# GraduatedDesign_03.net
KiCad netlist of a schematic drawn in Altium Designer
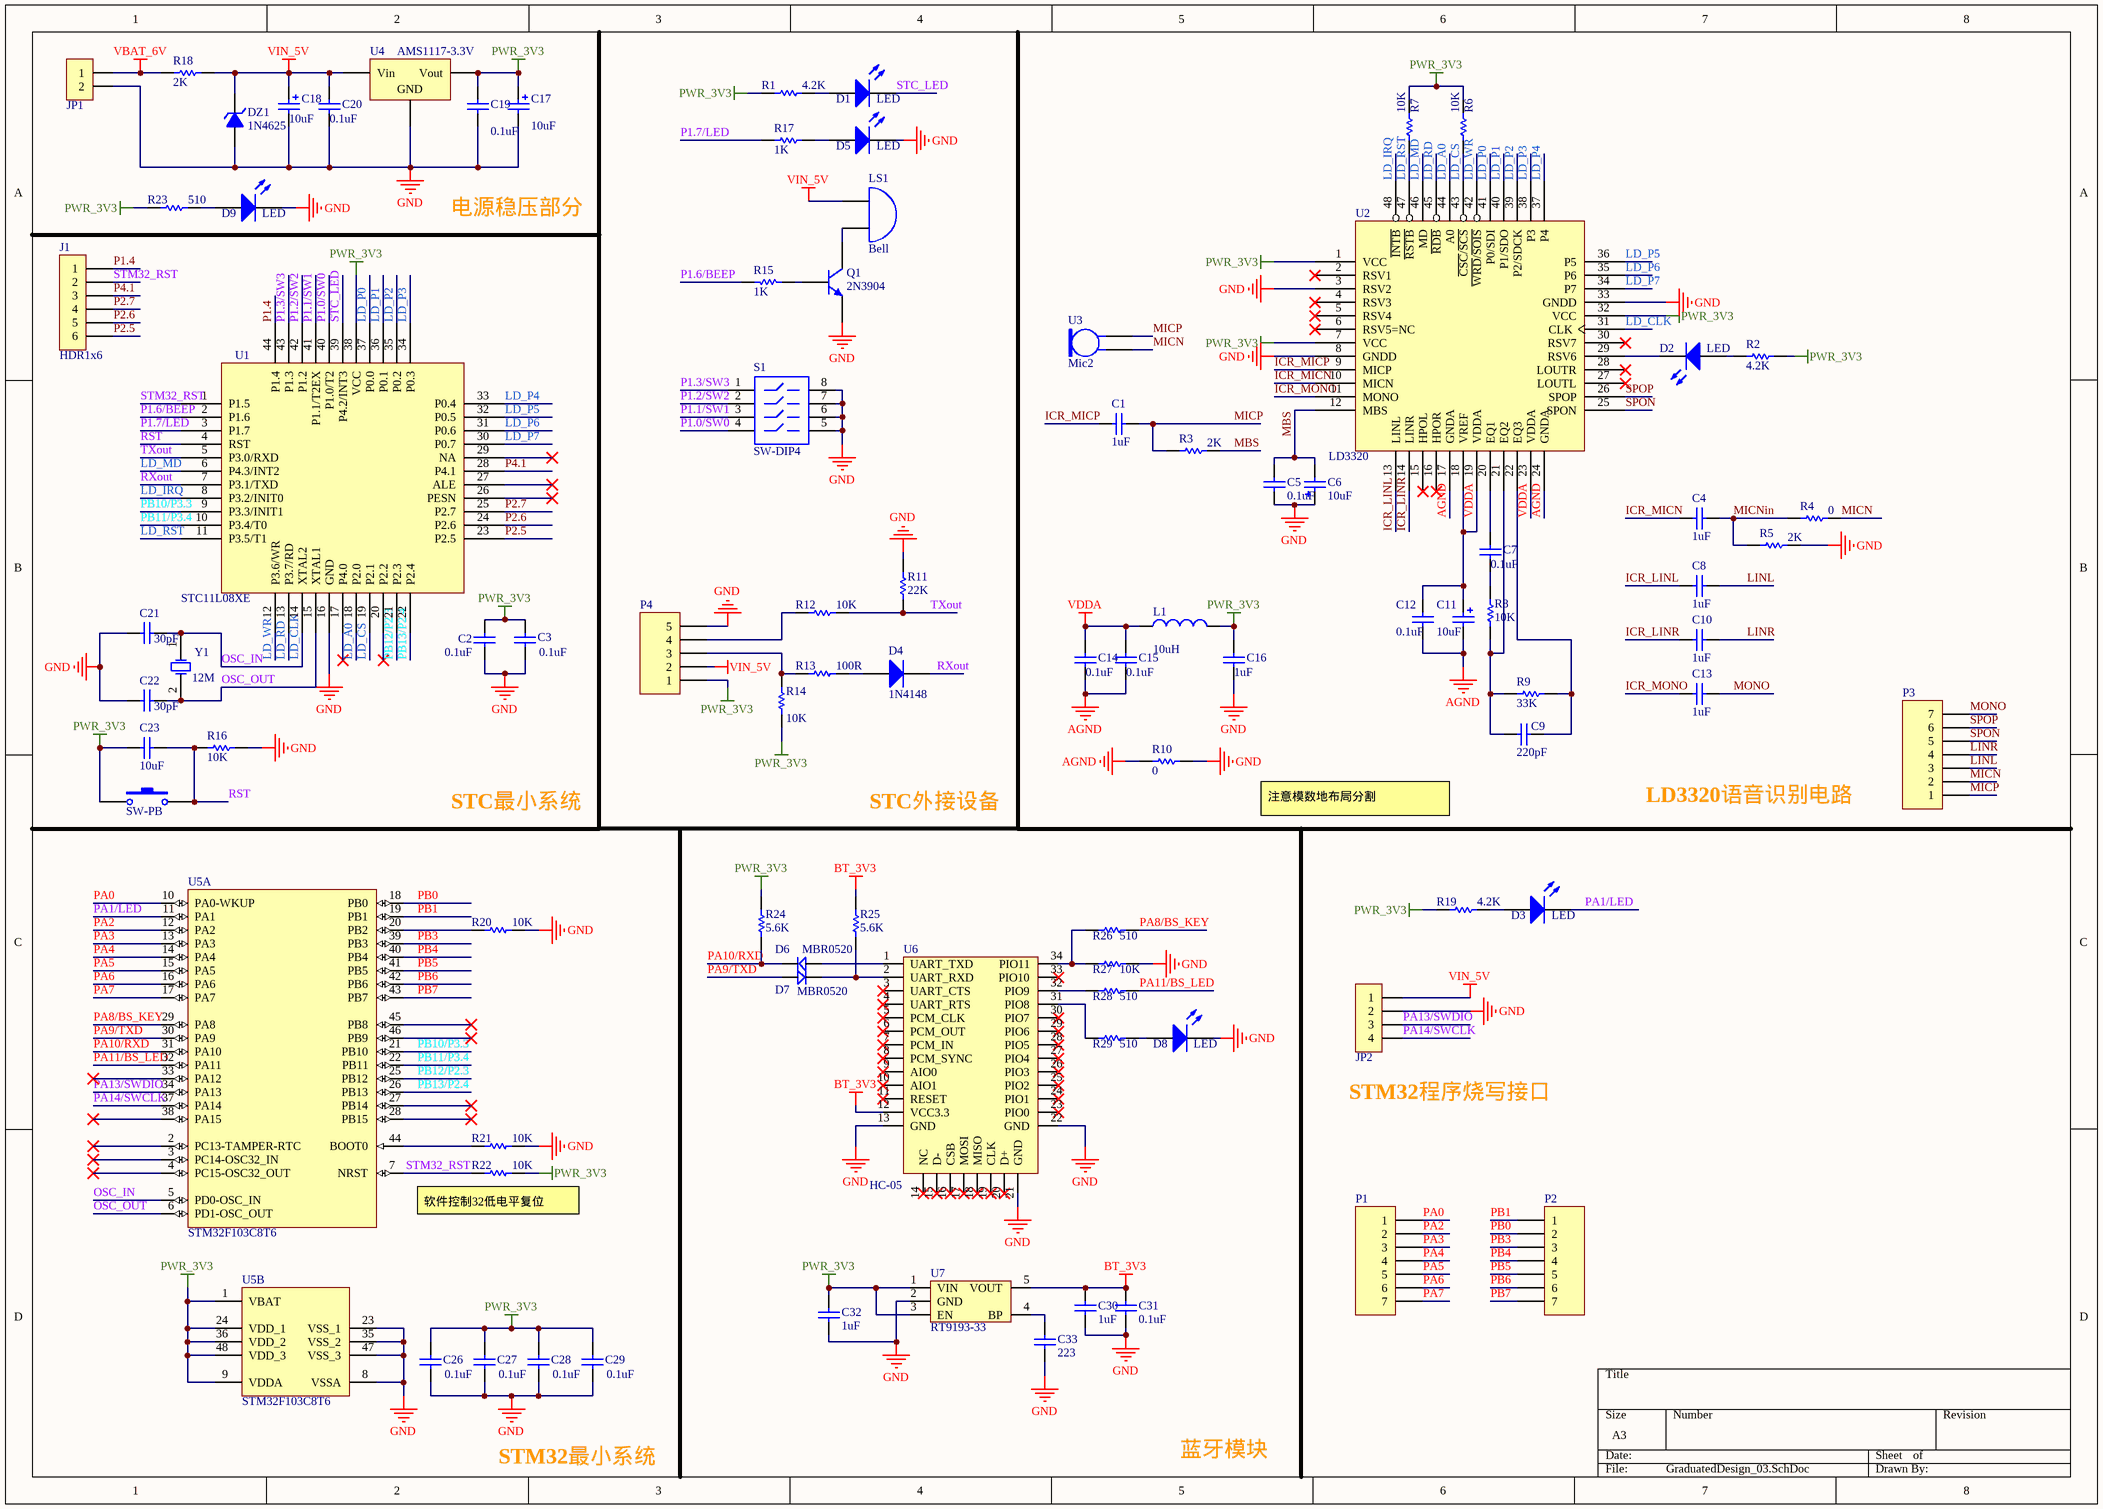
[diagram p0: GraduatedDesign_03.SchDoc]

(export (version "E")
  (design (tool "Eeschema 10.0.6"))
  (components
    (comp (ref "C1")
      (value "1uF")
      (footprint "C0603")
      (description "Capacitor")
      (fields (field (name "Comment") "Cap"))
      (libsource (lib "Miscellaneous Devices") (part "Cap"))
    )
    (comp (ref "C2")
      (value "0.1uF")
      (footprint "C0603")
      (description "Capacitor")
      (fields (field (name "Comment") "Cap"))
      (libsource (lib "Miscellaneous Devices") (part "Cap"))
    )
    (comp (ref "C3")
      (value "0.1uF")
      (footprint "C0603")
      (description "Capacitor")
      (fields (field (name "Comment") "Cap"))
      (libsource (lib "Miscellaneous Devices") (part "Cap"))
    )
    (comp (ref "C4")
      (value "1uF")
      (footprint "C0603")
      (description "Capacitor")
      (fields (field (name "Comment") "Cap"))
      (libsource (lib "Miscellaneous Devices") (part "Cap"))
    )
    (comp (ref "C5")
      (value "0.1uF")
      (footprint "C0603")
      (description "Capacitor")
      (fields (field (name "Comment") "Cap"))
      (libsource (lib "Miscellaneous Devices") (part "Cap"))
    )
    (comp (ref "C6")
      (value "10uF")
      (footprint "C3216")
      (description "Polarized Capacitor (Axial)")
      (fields (field (name "Comment") "Cap Pol2"))
      (libsource (lib "Miscellaneous Devices") (part "Cap Pol2"))
    )
    (comp (ref "C7")
      (value "0.1uF")
      (footprint "C0603")
      (description "Capacitor")
      (fields (field (name "Comment") "Cap"))
      (libsource (lib "Miscellaneous Devices") (part "Cap"))
    )
    (comp (ref "C8")
      (value "1uF")
      (footprint "C0603")
      (description "Capacitor")
      (fields (field (name "Comment") "Cap"))
      (libsource (lib "Miscellaneous Devices") (part "Cap"))
    )
    (comp (ref "C9")
      (value "220pF")
      (footprint "C0603")
      (description "Capacitor")
      (fields (field (name "Comment") "Cap"))
      (libsource (lib "Miscellaneous Devices") (part "Cap"))
    )
    (comp (ref "C10")
      (value "1uF")
      (footprint "C0603")
      (description "Capacitor")
      (fields (field (name "Comment") "Cap"))
      (libsource (lib "Miscellaneous Devices") (part "Cap"))
    )
    (comp (ref "C11")
      (value "10uF")
      (footprint "C3216")
      (description "Polarized Capacitor (Axial)")
      (fields (field (name "Comment") "Cap Pol2"))
      (libsource (lib "Miscellaneous Devices") (part "Cap Pol2"))
    )
    (comp (ref "C12")
      (value "0.1uF")
      (footprint "C0603")
      (description "Capacitor")
      (fields (field (name "Comment") "Cap"))
      (libsource (lib "Miscellaneous Devices") (part "Cap"))
    )
    (comp (ref "C13")
      (value "1uF")
      (footprint "C0603")
      (description "Capacitor")
      (fields (field (name "Comment") "Cap"))
      (libsource (lib "Miscellaneous Devices") (part "Cap"))
    )
    (comp (ref "C14")
      (value "0.1uF")
      (footprint "C0603")
      (description "Capacitor")
      (fields (field (name "Comment") "Cap"))
      (libsource (lib "Miscellaneous Devices") (part "Cap"))
    )
    (comp (ref "C15")
      (value "0.1uF")
      (footprint "C0603")
      (description "Capacitor")
      (fields (field (name "Comment") "Cap"))
      (libsource (lib "Miscellaneous Devices") (part "Cap"))
    )
    (comp (ref "C16")
      (value "1uF")
      (footprint "C0603")
      (description "Capacitor")
      (fields (field (name "Comment") "Cap"))
      (libsource (lib "Miscellaneous Devices") (part "Cap"))
    )
    (comp (ref "C17")
      (value "10uF")
      (footprint "C3216")
      (description "Polarized Capacitor (Axial)")
      (fields (field (name "Comment") "Cap Pol2"))
      (libsource (lib "Miscellaneous Devices") (part "Cap Pol2"))
    )
    (comp (ref "C18")
      (value "10uF")
      (footprint "C3216")
      (description "Polarized Capacitor (Axial)")
      (fields (field (name "Comment") "Cap Pol2"))
      (libsource (lib "Miscellaneous Devices") (part "Cap Pol2"))
    )
    (comp (ref "C19")
      (value "0.1uF")
      (footprint "C0603")
      (description "Capacitor")
      (fields (field (name "Comment") "Cap"))
      (libsource (lib "Miscellaneous Devices") (part "Cap"))
    )
    (comp (ref "C20")
      (value "0.1uF")
      (footprint "C0603")
      (description "Capacitor")
      (fields (field (name "Comment") "Cap"))
      (libsource (lib "Miscellaneous Devices") (part "Cap"))
    )
    (comp (ref "C21")
      (value "30pF")
      (footprint "C0603")
      (description "Capacitor")
      (fields (field (name "Comment") "Cap"))
      (libsource (lib "Miscellaneous Devices") (part "Cap"))
    )
    (comp (ref "C22")
      (value "30pF")
      (footprint "C0603")
      (description "Capacitor")
      (fields (field (name "Comment") "Cap"))
      (libsource (lib "Miscellaneous Devices") (part "Cap"))
    )
    (comp (ref "C23")
      (value "10uF")
      (footprint "C0603")
      (description "Capacitor")
      (fields (field (name "Comment") "Cap"))
      (libsource (lib "Miscellaneous Devices") (part "Cap"))
    )
    (comp (ref "C26")
      (value "0.1uF")
      (footprint "C0603")
      (description "Capacitor")
      (fields (field (name "Comment") "Cap"))
      (libsource (lib "Miscellaneous Devices") (part "Cap"))
    )
    (comp (ref "C27")
      (value "0.1uF")
      (footprint "C0603")
      (description "Capacitor")
      (fields (field (name "Comment") "Cap"))
      (libsource (lib "Miscellaneous Devices") (part "Cap"))
    )
    (comp (ref "C28")
      (value "0.1uF")
      (footprint "C0603")
      (description "Capacitor")
      (fields (field (name "Comment") "Cap"))
      (libsource (lib "Miscellaneous Devices") (part "Cap"))
    )
    (comp (ref "C29")
      (value "0.1uF")
      (footprint "C0603")
      (description "Capacitor")
      (fields (field (name "Comment") "Cap"))
      (libsource (lib "Miscellaneous Devices") (part "Cap"))
    )
    (comp (ref "C30")
      (value "1uF")
      (footprint "C0603")
      (description "Capacitor")
      (fields (field (name "Comment") "Cap"))
      (libsource (lib "Miscellaneous Devices") (part "Cap"))
    )
    (comp (ref "C31")
      (value "0.1uF")
      (footprint "C0603")
      (description "Capacitor")
      (fields (field (name "Comment") "Cap"))
      (libsource (lib "Miscellaneous Devices") (part "Cap"))
    )
    (comp (ref "C32")
      (value "1uF")
      (footprint "C0603")
      (description "Capacitor")
      (fields (field (name "Comment") "Cap"))
      (libsource (lib "Miscellaneous Devices") (part "Cap"))
    )
    (comp (ref "C33")
      (value "223")
      (footprint "C0603")
      (description "Capacitor")
      (fields (field (name "Comment") "Cap"))
      (libsource (lib "Miscellaneous Devices") (part "Cap"))
    )
    (comp (ref "D1")
      (value "LED")
      (footprint "0603LED_GREEN")
      (description "Typical INFRARED GaAs LED")
      (libsource (lib "Miscellaneous Devices") (part "LED0"))
    )
    (comp (ref "D2")
      (value "LED")
      (footprint "0603LED_RED")
      (description "Typical INFRARED GaAs LED")
      (libsource (lib "Miscellaneous Devices") (part "LED0"))
    )
    (comp (ref "D3")
      (value "LED")
      (footprint "0603LED_GREEN")
      (description "Typical INFRARED GaAs LED")
      (libsource (lib "Miscellaneous Devices") (part "LED0"))
    )
    (comp (ref "D4")
      (value "1N4148")
      (footprint "D1206")
      (description "High Conductance Fast Diode")
      (libsource (lib "Miscellaneous Devices") (part "Diode 1N4148"))
    )
    (comp (ref "D5")
      (value "LED")
      (footprint "0603LED_GREEN")
      (description "Typical INFRARED GaAs LED")
      (libsource (lib "Miscellaneous Devices") (part "LED0"))
    )
    (comp (ref "D6")
      (value "MBR0520")
      (footprint "SOD-123")
      (description "1N4148")
      (libsource (lib "ATK-HC05-V1.3") (part "D"))
    )
    (comp (ref "D7")
      (value "MBR0520")
      (footprint "SOD-123")
      (description "1N4148")
      (libsource (lib "ATK-HC05-V1.3") (part "D"))
    )
    (comp (ref "D8")
      (value "LED")
      (footprint "0603LED_GREEN")
      (description "Typical INFRARED GaAs LED")
      (libsource (lib "Miscellaneous Devices") (part "LED0"))
    )
    (comp (ref "D9")
      (value "LED")
      (footprint "0603LED_GREEN")
      (description "Typical INFRARED GaAs LED")
      (libsource (lib "Miscellaneous Devices") (part "LED0"))
    )
    (comp (ref "DZ1")
      (value "1N4625")
      (footprint "SOD-323")
      (description "5.1V/0.5W稳压管")
      (libsource (lib "二极管-整流桥") (part "1N4625"))
    )
    (comp (ref "J1")
      (value "HDR1x6")
      (footprint "HDR1X6")
      (description "Connector")
      (libsource (lib "General") (part "HDR1x6"))
    )
    (comp (ref "JP1")
      (value "HDR-1X2")
      (footprint "HDR1X2")
      (description "2P接插件")
      (libsource (lib "接插件") (part "Header 2"))
    )
    (comp (ref "JP2")
      (value "HDR-1X4")
      (footprint "HDR1X4")
      (description "4P接插件")
      (libsource (lib "接插件") (part "Header 4"))
    )
    (comp (ref "L1")
      (value "10uH")
      (footprint "L0805")
      (description "Inductor")
      (libsource (lib "Miscellaneous Devices") (part "Inductor"))
    )
    (comp (ref "LS1")
      (value "Bell")
      (footprint "BELL")
      (description "Electrical Bell")
      (libsource (lib "Miscellaneous Devices") (part "Bell"))
    )
    (comp (ref "P1")
      (value "Header 7H")
      (footprint "Miscellaneous Connectors:HDR1X7")
      (description "Header, 7-Pin, Right Angle")
      (libsource (lib "") (part "Header 7H_1"))
    )
    (comp (ref "P2")
      (value "Header 7H")
      (footprint "Miscellaneous Connectors:HDR1X7")
      (description "Header, 7-Pin, Right Angle")
      (libsource (lib "") (part "Header 7H_2"))
    )
    (comp (ref "P3")
      (value "Header 7H")
      (footprint "Miscellaneous Connectors:HDR1X7")
      (description "Header, 7-Pin, Right Angle")
      (libsource (lib "Miscellaneous Connectors") (part "Header 7H"))
    )
    (comp (ref "P4")
      (value "Header 5H")
      (footprint "Miscellaneous Connectors:HDR1X5")
      (description "Header, 5-Pin, Right Angle")
      (libsource (lib "Miscellaneous Connectors") (part "Header 5H"))
    )
    (comp (ref "Q1")
      (value "2N3904")
      (footprint "SOT-23")
      (description "NPN General Purpose Amplifier")
      (libsource (lib "Miscellaneous Devices") (part "2N3904"))
    )
    (comp (ref "R1")
      (value "4.2K")
      (footprint "R0603")
      (description "Resistor")
      (fields (field (name "Comment") "Res1"))
      (libsource (lib "Miscellaneous Devices") (part "Res1"))
    )
    (comp (ref "R2")
      (value "4.2K")
      (footprint "R0603")
      (description "Resistor")
      (fields (field (name "Comment") "Res1"))
      (libsource (lib "Miscellaneous Devices") (part "Res1"))
    )
    (comp (ref "R3")
      (value "2K")
      (footprint "R0603")
      (description "Resistor")
      (fields (field (name "Comment") "Res1"))
      (libsource (lib "Miscellaneous Devices") (part "Res1"))
    )
    (comp (ref "R4")
      (value "0")
      (footprint "R0603")
      (description "Resistor")
      (fields (field (name "Comment") "Res1"))
      (libsource (lib "Miscellaneous Devices") (part "Res1"))
    )
    (comp (ref "R5")
      (value "2K")
      (footprint "R0603")
      (description "Resistor")
      (fields (field (name "Comment") "Res1"))
      (libsource (lib "Miscellaneous Devices") (part "Res1"))
    )
    (comp (ref "R6")
      (value "10K")
      (footprint "R0603")
      (description "Resistor")
      (fields (field (name "Comment") "Res1"))
      (libsource (lib "Miscellaneous Devices") (part "Res1"))
    )
    (comp (ref "R7")
      (value "10K")
      (footprint "R0603")
      (description "Resistor")
      (fields (field (name "Comment") "Res1"))
      (libsource (lib "Miscellaneous Devices") (part "Res1"))
    )
    (comp (ref "R8")
      (value "10K")
      (footprint "R0603")
      (description "Resistor")
      (fields (field (name "Comment") "Res1"))
      (libsource (lib "Miscellaneous Devices") (part "Res1"))
    )
    (comp (ref "R9")
      (value "33K")
      (footprint "R0603")
      (description "Resistor")
      (fields (field (name "Comment") "Res1"))
      (libsource (lib "Miscellaneous Devices") (part "Res1"))
    )
    (comp (ref "R10")
      (value "0")
      (footprint "R0603")
      (description "Resistor")
      (fields (field (name "Comment") "Res1"))
      (libsource (lib "Miscellaneous Devices") (part "Res1"))
    )
    (comp (ref "R11")
      (value "22K")
      (footprint "R0603")
      (description "Semiconductor Resistor")
      (fields (field (name "Comment") "Res Semi"))
      (libsource (lib "Miscellaneous Devices") (part "Res Semi"))
    )
    (comp (ref "R12")
      (value "10K")
      (footprint "R0603")
      (description "Semiconductor Resistor")
      (fields (field (name "Comment") "Res Semi"))
      (libsource (lib "Miscellaneous Devices") (part "Res Semi"))
    )
    (comp (ref "R13")
      (value "100R")
      (footprint "R0603")
      (description "Semiconductor Resistor")
      (fields (field (name "Comment") "Res Semi"))
      (libsource (lib "Miscellaneous Devices") (part "Res Semi"))
    )
    (comp (ref "R14")
      (value "10K")
      (footprint "R0603")
      (description "Semiconductor Resistor")
      (fields (field (name "Comment") "Res Semi"))
      (libsource (lib "Miscellaneous Devices") (part "Res Semi"))
    )
    (comp (ref "R15")
      (value "1K")
      (footprint "R0603")
      (description "Resistor")
      (fields (field (name "Comment") "Res1"))
      (libsource (lib "Miscellaneous Devices") (part "Res1"))
    )
    (comp (ref "R16")
      (value "10K")
      (footprint "R0603")
      (description "Resistor")
      (fields (field (name "Comment") "Res1"))
      (libsource (lib "Miscellaneous Devices") (part "Res1"))
    )
    (comp (ref "R17")
      (value "1K")
      (footprint "R0603")
      (description "Resistor")
      (fields (field (name "Comment") "Res1"))
      (libsource (lib "Miscellaneous Devices") (part "Res1"))
    )
    (comp (ref "R18")
      (value "2K")
      (footprint "R0603")
      (description "Resistor")
      (fields (field (name "Comment") "Res1"))
      (libsource (lib "Miscellaneous Devices") (part "Res1"))
    )
    (comp (ref "R19")
      (value "4.2K")
      (footprint "R0603")
      (description "Resistor")
      (fields (field (name "Comment") "Res1"))
      (libsource (lib "Miscellaneous Devices") (part "Res1"))
    )
    (comp (ref "R20")
      (value "10K")
      (footprint "R0603")
      (description "Resistor")
      (fields (field (name "Comment") "Res1"))
      (libsource (lib "Miscellaneous Devices") (part "Res1"))
    )
    (comp (ref "R21")
      (value "10K")
      (footprint "R0603")
      (description "Resistor")
      (fields (field (name "Comment") "Res1"))
      (libsource (lib "Miscellaneous Devices") (part "Res1"))
    )
    (comp (ref "R22")
      (value "10K")
      (footprint "R0603")
      (description "Resistor")
      (fields (field (name "Comment") "Res1"))
      (libsource (lib "Miscellaneous Devices") (part "Res1"))
    )
    (comp (ref "R23")
      (value "510")
      (footprint "R0603")
      (description "Resistor")
      (fields (field (name "Comment") "Res1"))
      (libsource (lib "Miscellaneous Devices") (part "Res1"))
    )
    (comp (ref "R24")
      (value "5.6K")
      (footprint "R0603")
      (description "Resistor")
      (fields (field (name "Comment") "Res1"))
      (libsource (lib "Miscellaneous Devices") (part "Res1"))
    )
    (comp (ref "R25")
      (value "5.6K")
      (footprint "R0603")
      (description "Resistor")
      (fields (field (name "Comment") "Res1"))
      (libsource (lib "Miscellaneous Devices") (part "Res1"))
    )
    (comp (ref "R26")
      (value "510")
      (footprint "R0603")
      (description "Resistor")
      (fields (field (name "Comment") "Res1"))
      (libsource (lib "Miscellaneous Devices") (part "Res1"))
    )
    (comp (ref "R27")
      (value "10K")
      (footprint "R0603")
      (description "Resistor")
      (fields (field (name "Comment") "Res1"))
      (libsource (lib "Miscellaneous Devices") (part "Res1"))
    )
    (comp (ref "R28")
      (value "510")
      (footprint "R0603")
      (description "Resistor")
      (fields (field (name "Comment") "Res1"))
      (libsource (lib "Miscellaneous Devices") (part "Res1"))
    )
    (comp (ref "R29")
      (value "510")
      (footprint "R0603")
      (description "Resistor")
      (fields (field (name "Comment") "Res1"))
      (libsource (lib "Miscellaneous Devices") (part "Res1"))
    )
    (comp (ref "S1")
      (value "SW-DIP4")
      (footprint "DIP-8")
      (description "DIP Switch")
      (libsource (lib "Miscellaneous Devices") (part "SW-DIP4"))
    )
    (comp (ref "S2")
      (value "SW-PB")
      (footprint "SPST-2")
      (description "Switch")
      (libsource (lib "Miscellaneous Devices") (part "SW-PB"))
    )
    (comp (ref "U1")
      (value "STC11L08XE")
      (footprint "QFP-44")
      (libsource (lib "STC11L08XE") (part "STC11L08XE"))
    )
    (comp (ref "U2") (value "LD3320") (footprint "LD3320A") (libsource (lib "STC11L08XE") (part "LD3320A")))
    (comp (ref "U3")
      (value "Mic2")
      (footprint "PIN2")
      (description "Microphone")
      (libsource (lib "Miscellaneous Devices") (part "Mic2"))
    )
    (comp (ref "U4")
      (value "AMS1117-3.3V")
      (footprint "SOT223")
      (description "Voltage Regulator")
      (libsource (lib "Miscellaneous Devices") (part "Volt Reg"))
    )
    (comp (ref "U5")
      (value "STM32F103C8T6")
      (footprint "LQFP48_M")
      (libsource (lib "STMicroelectronics STM32 F1") (part "STM32F103C8T6"))
    )
    (comp (ref "U6")
      (value "HC-05")
      (footprint "HC-0x")
      (description "蓝牙串口模块")
      (libsource (lib "ATK-HC05-V1.3") (part "HC-05"))
    )
    (comp (ref "U7")
      (value "RT9193-33")
      (footprint "SOT-23-5")
      (description "3.3V超低压差LDO")
      (libsource (lib "ATK-HC05-V1.3") (part "RT9193-33"))
    )
    (comp (ref "Y1")
      (value "12M")
      (footprint "49/S_N")
      (description "Crystal Oscillator")
      (libsource (lib "Miscellaneous Devices") (part "XTAL"))
    )
  )
  (nets
    (net (code "1") (name "/ICR_LINL") (class "Default")
      (node (ref "C8") (pin "1") (pinfunction "1_1") (pintype "passive"))
      (node (ref "U2") (pin "13") (pinfunction "LINL_13") (pintype "passive"))
    )
    (net (code "2") (name "/ICR_LINR") (class "Default")
      (node (ref "C10") (pin "1") (pinfunction "1_1") (pintype "passive"))
      (node (ref "U2") (pin "14") (pinfunction "LINR_14") (pintype "passive"))
    )
    (net (code "3") (name "/ICR_MICN") (class "Default")
      (node (ref "C4") (pin "1") (pinfunction "1_1") (pintype "passive"))
      (node (ref "U2") (pin "10") (pinfunction "MICN_10") (pintype "passive"))
    )
    (net (code "4") (name "/ICR_MICP") (class "Default")
      (node (ref "C1") (pin "1") (pinfunction "1_1") (pintype "passive"))
      (node (ref "U2") (pin "9") (pinfunction "MICP_9") (pintype "passive"))
    )
    (net (code "5") (name "/ICR_MONO") (class "Default")
      (node (ref "C13") (pin "1") (pinfunction "1_1") (pintype "passive"))
      (node (ref "U2") (pin "11") (pinfunction "MONO_11") (pintype "passive"))
    )
    (net (code "6") (name "/LD_A0") (class "Default")
      (node (ref "U1") (pin "18") (pinfunction "P2.0_18") (pintype "passive"))
      (node (ref "U2") (pin "44") (pinfunction "A0_44") (pintype "passive"))
    )
    (net (code "7") (name "/LD_CLK") (class "Default")
      (node (ref "C21") (pin "2") (pinfunction "2_2") (pintype "passive"))
      (node (ref "U1") (pin "14") (pinfunction "XTAL2_14") (pintype "passive"))
      (node (ref "U2") (pin "31") (pinfunction "CLK_31") (pintype "passive"))
      (node (ref "U5") (pin "5") (pinfunction "PD0-OSC_IN_5") (pintype "bidirectional"))
      (node (ref "Y1") (pin "1") (pinfunction "OSC1_1") (pintype "passive"))
    )
    (net (code "8") (name "/LD_CS") (class "Default")
      (node (ref "R6") (pin "2") (pinfunction "2_2") (pintype "passive"))
      (node (ref "U1") (pin "19") (pinfunction "P2.1_19") (pintype "passive"))
      (node (ref "U2") (pin "43") (pinfunction "~{CSC}/~{SCS}_43") (pintype "passive"))
    )
    (net (code "9") (name "/LD_IRQ") (class "Default")
      (node (ref "U1") (pin "8") (pinfunction "P3.2/INIT0_8") (pintype "passive"))
      (node (ref "U2") (pin "48") (pinfunction "~{INTB}_48") (pintype "passive"))
    )
    (net (code "10") (name "/LD_MD") (class "Default")
      (node (ref "U1") (pin "6") (pinfunction "P4.3/INT2_6") (pintype "passive"))
      (node (ref "U2") (pin "46") (pinfunction "MD_46") (pintype "passive"))
    )
    (net (code "11") (name "/LD_P0") (class "Default")
      (node (ref "U1") (pin "37") (pinfunction "P0.0_37") (pintype "passive"))
      (node (ref "U2") (pin "41") (pinfunction "P0/SDI_41") (pintype "passive"))
    )
    (net (code "12") (name "/LD_P1") (class "Default")
      (node (ref "U1") (pin "36") (pinfunction "P0.1_36") (pintype "passive"))
      (node (ref "U2") (pin "40") (pinfunction "P1/SDO_40") (pintype "passive"))
    )
    (net (code "13") (name "/LD_P2") (class "Default")
      (node (ref "U1") (pin "35") (pinfunction "P0.2_35") (pintype "passive"))
      (node (ref "U2") (pin "39") (pinfunction "P2/SDCK_39") (pintype "passive"))
    )
    (net (code "14") (name "/LD_P3") (class "Default")
      (node (ref "U1") (pin "34") (pinfunction "P0.3_34") (pintype "passive"))
      (node (ref "U2") (pin "38") (pinfunction "P3_38") (pintype "passive"))
    )
    (net (code "15") (name "/LD_P4") (class "Default")
      (node (ref "U1") (pin "33") (pinfunction "P0.4_33") (pintype "passive"))
      (node (ref "U2") (pin "37") (pinfunction "P4_37") (pintype "passive"))
    )
    (net (code "16") (name "/LD_P5") (class "Default")
      (node (ref "U1") (pin "32") (pinfunction "P0.5_32") (pintype "passive"))
      (node (ref "U2") (pin "36") (pinfunction "P5_36") (pintype "passive"))
    )
    (net (code "17") (name "/LD_P6") (class "Default")
      (node (ref "U1") (pin "31") (pinfunction "P0.6_31") (pintype "passive"))
      (node (ref "U2") (pin "35") (pinfunction "P6_35") (pintype "passive"))
    )
    (net (code "18") (name "/LD_P7") (class "Default")
      (node (ref "U1") (pin "30") (pinfunction "P0.7_30") (pintype "passive"))
      (node (ref "U2") (pin "34") (pinfunction "P7_34") (pintype "passive"))
    )
    (net (code "19") (name "/LD_RD") (class "Default")
      (node (ref "U1") (pin "13") (pinfunction "P3.7/RD_13") (pintype "passive"))
      (node (ref "U2") (pin "45") (pinfunction "~{RDB}_45") (pintype "passive"))
    )
    (net (code "20") (name "/LD_RST") (class "Default")
      (node (ref "R7") (pin "2") (pinfunction "2_2") (pintype "passive"))
      (node (ref "U1") (pin "11") (pinfunction "P3.5/T1_11") (pintype "passive"))
      (node (ref "U2") (pin "47") (pinfunction "~{RSTB}_47") (pintype "passive"))
    )
    (net (code "21") (name "/LD_WR") (class "Default")
      (node (ref "U1") (pin "12") (pinfunction "P3.6/WR_12") (pintype "passive"))
      (node (ref "U2") (pin "42") (pinfunction "~{WRD}/~{SOIS}_42") (pintype "passive"))
    )
    (net (code "22") (name "/LINL") (class "Default")
      (node (ref "C8") (pin "2") (pinfunction "2_2") (pintype "passive"))
      (node (ref "P3") (pin "3") (pinfunction "3_3") (pintype "passive"))
    )
    (net (code "23") (name "/LINR") (class "Default")
      (node (ref "C10") (pin "2") (pinfunction "2_2") (pintype "passive"))
      (node (ref "P3") (pin "4") (pinfunction "4_4") (pintype "passive"))
    )
    (net (code "24") (name "/MBS") (class "Default")
      (node (ref "C5") (pin "1") (pinfunction "1_1") (pintype "passive"))
      (node (ref "C6") (pin "2") (pinfunction "2_2") (pintype "passive"))
      (node (ref "R3") (pin "2") (pinfunction "2_2") (pintype "passive"))
      (node (ref "U2") (pin "12") (pinfunction "MBS_12") (pintype "passive"))
    )
    (net (code "25") (name "/MICN") (class "Default")
      (node (ref "P3") (pin "2") (pinfunction "2_2") (pintype "passive"))
      (node (ref "R4") (pin "2") (pinfunction "2_2") (pintype "passive"))
      (node (ref "U3") (pin "1") (pinfunction "1_1") (pintype "passive"))
    )
    (net (code "26") (name "/MICNin") (class "Default")
      (node (ref "C4") (pin "2") (pinfunction "2_2") (pintype "passive"))
      (node (ref "R4") (pin "1") (pinfunction "1_1") (pintype "passive"))
      (node (ref "R5") (pin "1") (pinfunction "1_1") (pintype "passive"))
    )
    (net (code "27") (name "/MICP") (class "Default")
      (node (ref "C1") (pin "2") (pinfunction "2_2") (pintype "passive"))
      (node (ref "P3") (pin "1") (pinfunction "1_1") (pintype "passive"))
      (node (ref "R3") (pin "1") (pinfunction "1_1") (pintype "passive"))
      (node (ref "U3") (pin "2") (pinfunction "2_2") (pintype "passive"))
    )
    (net (code "28") (name "/MONO") (class "Default")
      (node (ref "C13") (pin "2") (pinfunction "2_2") (pintype "passive"))
      (node (ref "P3") (pin "7") (pinfunction "7_7") (pintype "passive"))
    )
    (net (code "29") (name "/OSC_OUT") (class "Default")
      (node (ref "C22") (pin "2") (pinfunction "2_2") (pintype "passive"))
      (node (ref "U1") (pin "15") (pinfunction "XTAL1_15") (pintype "passive"))
      (node (ref "U5") (pin "6") (pinfunction "PD1-OSC_OUT_6") (pintype "bidirectional"))
      (node (ref "Y1") (pin "2") (pinfunction "OSC2_2") (pintype "passive"))
    )
    (net (code "30") (name "/P1.0{slash}SW0") (class "Default")
      (node (ref "S1") (pin "4") (pinfunction "4_4") (pintype "passive"))
      (node (ref "U1") (pin "40") (pinfunction "P1.0/T2_40") (pintype "passive"))
    )
    (net (code "31") (name "/P1.1{slash}SW1") (class "Default")
      (node (ref "S1") (pin "3") (pinfunction "3_3") (pintype "passive"))
      (node (ref "U1") (pin "41") (pinfunction "P1.1/T2EX_41") (pintype "passive"))
    )
    (net (code "32") (name "/P1.2{slash}SW2") (class "Default")
      (node (ref "S1") (pin "2") (pinfunction "2_2") (pintype "passive"))
      (node (ref "U1") (pin "42") (pinfunction "P1.2_42") (pintype "passive"))
    )
    (net (code "33") (name "/P1.3{slash}SW3") (class "Default")
      (node (ref "S1") (pin "1") (pinfunction "1_1") (pintype "passive"))
      (node (ref "U1") (pin "43") (pinfunction "P1.3_43") (pintype "passive"))
    )
    (net (code "34") (name "/P1.4") (class "Default")
      (node (ref "J1") (pin "1") (pinfunction "1_1") (pintype "passive"))
      (node (ref "U1") (pin "44") (pinfunction "P1.4_44") (pintype "passive"))
    )
    (net (code "35") (name "/P1.6{slash}BEEP") (class "Default")
      (node (ref "R15") (pin "1") (pinfunction "1_1") (pintype "passive"))
      (node (ref "U1") (pin "2") (pinfunction "P1.6_2") (pintype "passive"))
    )
    (net (code "36") (name "/P1.7{slash}LED") (class "Default")
      (node (ref "R17") (pin "1") (pinfunction "1_1") (pintype "passive"))
      (node (ref "U1") (pin "3") (pinfunction "P1.7_3") (pintype "passive"))
    )
    (net (code "37") (name "/P2.5") (class "Default")
      (node (ref "J1") (pin "6") (pinfunction "6_6") (pintype "passive"))
      (node (ref "U1") (pin "23") (pinfunction "P2.5_23") (pintype "passive"))
    )
    (net (code "38") (name "/P2.6") (class "Default")
      (node (ref "J1") (pin "5") (pinfunction "5_5") (pintype "passive"))
      (node (ref "U1") (pin "24") (pinfunction "P2.6_24") (pintype "passive"))
    )
    (net (code "39") (name "/P2.7") (class "Default")
      (node (ref "J1") (pin "4") (pinfunction "4_4") (pintype "passive"))
      (node (ref "U1") (pin "25") (pinfunction "P2.7_25") (pintype "passive"))
    )
    (net (code "40") (name "/P4.1") (class "Default")
      (node (ref "J1") (pin "3") (pinfunction "3_3") (pintype "passive"))
      (node (ref "U1") (pin "28") (pinfunction "P4.1_28") (pintype "passive"))
    )
    (net (code "41") (name "/PA0") (class "Default")
      (node (ref "P1") (pin "1") (pinfunction "1_1") (pintype "passive"))
      (node (ref "U5") (pin "10") (pinfunction "PA0-WKUP_10") (pintype "bidirectional"))
    )
    (net (code "42") (name "/PA1{slash}LED") (class "Default")
      (node (ref "D3") (pin "2") (pinfunction "K_2") (pintype "passive"))
      (node (ref "U5") (pin "11") (pinfunction "PA1_11") (pintype "bidirectional"))
    )
    (net (code "43") (name "/PA2") (class "Default")
      (node (ref "P1") (pin "2") (pinfunction "2_2") (pintype "passive"))
      (node (ref "U5") (pin "12") (pinfunction "PA2_12") (pintype "bidirectional"))
    )
    (net (code "44") (name "/PA3") (class "Default")
      (node (ref "P1") (pin "3") (pinfunction "3_3") (pintype "passive"))
      (node (ref "U5") (pin "13") (pinfunction "PA3_13") (pintype "bidirectional"))
    )
    (net (code "45") (name "/PA4") (class "Default")
      (node (ref "P1") (pin "4") (pinfunction "4_4") (pintype "passive"))
      (node (ref "U5") (pin "14") (pinfunction "PA4_14") (pintype "bidirectional"))
    )
    (net (code "46") (name "/PA5") (class "Default")
      (node (ref "P1") (pin "5") (pinfunction "5_5") (pintype "passive"))
      (node (ref "U5") (pin "15") (pinfunction "PA5_15") (pintype "bidirectional"))
    )
    (net (code "47") (name "/PA6") (class "Default")
      (node (ref "P1") (pin "6") (pinfunction "6_6") (pintype "passive"))
      (node (ref "U5") (pin "16") (pinfunction "PA6_16") (pintype "bidirectional"))
    )
    (net (code "48") (name "/PA7") (class "Default")
      (node (ref "P1") (pin "7") (pinfunction "7_7") (pintype "passive"))
      (node (ref "U5") (pin "17") (pinfunction "PA7_17") (pintype "bidirectional"))
    )
    (net (code "49") (name "/PA8{slash}BS_KEY") (class "Default")
      (node (ref "R26") (pin "1") (pinfunction "1_1") (pintype "passive"))
      (node (ref "U5") (pin "29") (pinfunction "PA8_29") (pintype "bidirectional"))
    )
    (net (code "50") (name "/PA9{slash}TXD") (class "Default")
      (node (ref "D7") (pin "1") (pintype "passive"))
      (node (ref "U5") (pin "30") (pinfunction "PA9_30") (pintype "bidirectional"))
    )
    (net (code "51") (name "/PA10{slash}RXD") (class "Default")
      (node (ref "D6") (pin "2") (pintype "passive"))
      (node (ref "R24") (pin "2") (pinfunction "2_2") (pintype "passive"))
      (node (ref "U5") (pin "31") (pinfunction "PA10_31") (pintype "bidirectional"))
    )
    (net (code "52") (name "/PA11{slash}BS_LED") (class "Default")
      (node (ref "R28") (pin "1") (pinfunction "1_1") (pintype "passive"))
      (node (ref "U5") (pin "32") (pinfunction "PA11_32") (pintype "bidirectional"))
    )
    (net (code "53") (name "/PA13{slash}SWDIO") (class "Default")
      (node (ref "JP2") (pin "3") (pinfunction "3_3") (pintype "passive"))
      (node (ref "U5") (pin "34") (pinfunction "PA13_34") (pintype "bidirectional"))
    )
    (net (code "54") (name "/PA14{slash}SWCLK") (class "Default")
      (node (ref "JP2") (pin "4") (pinfunction "4_4") (pintype "passive"))
      (node (ref "U5") (pin "37") (pinfunction "PA14_37") (pintype "bidirectional"))
    )
    (net (code "55") (name "/PB0") (class "Default")
      (node (ref "P2") (pin "2") (pinfunction "2_2") (pintype "passive"))
      (node (ref "U5") (pin "18") (pinfunction "PB0_18") (pintype "bidirectional"))
    )
    (net (code "56") (name "/PB1") (class "Default")
      (node (ref "P2") (pin "1") (pinfunction "1_1") (pintype "passive"))
      (node (ref "U5") (pin "19") (pinfunction "PB1_19") (pintype "bidirectional"))
    )
    (net (code "57") (name "/PB3") (class "Default")
      (node (ref "P2") (pin "3") (pinfunction "3_3") (pintype "passive"))
      (node (ref "U5") (pin "39") (pinfunction "PB3_39") (pintype "bidirectional"))
    )
    (net (code "58") (name "/PB4") (class "Default")
      (node (ref "P2") (pin "4") (pinfunction "4_4") (pintype "passive"))
      (node (ref "U5") (pin "40") (pinfunction "PB4_40") (pintype "bidirectional"))
    )
    (net (code "59") (name "/PB5") (class "Default")
      (node (ref "P2") (pin "5") (pinfunction "5_5") (pintype "passive"))
      (node (ref "U5") (pin "41") (pinfunction "PB5_41") (pintype "bidirectional"))
    )
    (net (code "60") (name "/PB6") (class "Default")
      (node (ref "P2") (pin "6") (pinfunction "6_6") (pintype "passive"))
      (node (ref "U5") (pin "42") (pinfunction "PB6_42") (pintype "bidirectional"))
    )
    (net (code "61") (name "/PB7") (class "Default")
      (node (ref "P2") (pin "7") (pinfunction "7_7") (pintype "passive"))
      (node (ref "U5") (pin "43") (pinfunction "PB7_43") (pintype "bidirectional"))
    )
    (net (code "62") (name "/PB10{slash}P3.3") (class "Default")
      (node (ref "U1") (pin "9") (pinfunction "P3.3/INIT1_9") (pintype "passive"))
      (node (ref "U5") (pin "21") (pinfunction "PB10_21") (pintype "bidirectional"))
    )
    (net (code "63") (name "/PB11{slash}P3.4") (class "Default")
      (node (ref "U1") (pin "10") (pinfunction "P3.4/T0_10") (pintype "passive"))
      (node (ref "U5") (pin "22") (pinfunction "PB11_22") (pintype "bidirectional"))
    )
    (net (code "64") (name "/PB12{slash}P2.3") (class "Default")
      (node (ref "U1") (pin "21") (pinfunction "P2.3_21") (pintype "passive"))
      (node (ref "U5") (pin "25") (pinfunction "PB12_25") (pintype "bidirectional"))
    )
    (net (code "65") (name "/PB13{slash}P2.4") (class "Default")
      (node (ref "U1") (pin "22") (pinfunction "P2.4_22") (pintype "passive"))
      (node (ref "U5") (pin "26") (pinfunction "PB13_26") (pintype "bidirectional"))
    )
    (net (code "66") (name "/RST") (class "Default")
      (node (ref "C23") (pin "1") (pinfunction "1_1") (pintype "passive"))
      (node (ref "R16") (pin "2") (pinfunction "2_2") (pintype "passive"))
      (node (ref "S2") (pin "2") (pinfunction "2_2") (pintype "passive"))
      (node (ref "U1") (pin "4") (pinfunction "RST_4") (pintype "passive"))
    )
    (net (code "67") (name "/RXout") (class "Default")
      (node (ref "D4") (pin "2") (pinfunction "K_2") (pintype "passive"))
      (node (ref "U1") (pin "7") (pinfunction "P3.1/TXD_7") (pintype "passive"))
    )
    (net (code "68") (name "/SPON") (class "Default")
      (node (ref "P3") (pin "5") (pinfunction "5_5") (pintype "passive"))
      (node (ref "U2") (pin "25") (pinfunction "SPON_25") (pintype "passive"))
    )
    (net (code "69") (name "/SPOP") (class "Default")
      (node (ref "P3") (pin "6") (pinfunction "6_6") (pintype "passive"))
      (node (ref "U2") (pin "26") (pinfunction "SPOP_26") (pintype "passive"))
    )
    (net (code "70") (name "/STC_LED") (class "Default")
      (node (ref "D1") (pin "2") (pinfunction "K_2") (pintype "passive"))
      (node (ref "U1") (pin "39") (pinfunction "P4.2/INT3_39") (pintype "passive"))
    )
    (net (code "71") (name "/STM32_RST") (class "Default")
      (node (ref "J1") (pin "2") (pinfunction "2_2") (pintype "passive"))
      (node (ref "R22") (pin "2") (pinfunction "2_2") (pintype "passive"))
      (node (ref "U1") (pin "1") (pinfunction "P1.5_1") (pintype "passive"))
      (node (ref "U5") (pin "7") (pinfunction "NRST_7") (pintype "bidirectional"))
    )
    (net (code "72") (name "/TXout") (class "Default")
      (node (ref "R11") (pin "1") (pinfunction "1_1") (pintype "passive"))
      (node (ref "R12") (pin "2") (pinfunction "2_2") (pintype "passive"))
      (node (ref "U1") (pin "5") (pinfunction "P3.0/RXD_5") (pintype "passive"))
    )
    (net (code "73") (name "AGND") (class "Default")
      (node (ref "C11") (pin "2") (pinfunction "2_2") (pintype "passive"))
      (node (ref "C12") (pin "1") (pinfunction "1_1") (pintype "passive"))
      (node (ref "C14") (pin "1") (pinfunction "1_1") (pintype "passive"))
      (node (ref "C15") (pin "1") (pinfunction "1_1") (pintype "passive"))
      (node (ref "R10") (pin "2") (pinfunction "2_2") (pintype "passive"))
      (node (ref "U2") (pin "17") (pinfunction "GNDA_17") (pintype "passive"))
      (node (ref "U2") (pin "24") (pinfunction "GNDA_24") (pintype "passive"))
    )
    (net (code "74") (name "BT_3V3") (class "Default")
      (node (ref "C30") (pin "1") (pinfunction "1_1") (pintype "passive"))
      (node (ref "C31") (pin "1") (pinfunction "1_1") (pintype "passive"))
      (node (ref "R25") (pin "1") (pinfunction "1_1") (pintype "passive"))
      (node (ref "U6") (pin "12") (pinfunction "VCC3.3_12") (pintype "passive"))
      (node (ref "U7") (pin "5") (pinfunction "VOUT_5") (pintype "passive"))
    )
    (net (code "75") (name "GND") (class "Default")
      (node (ref "C16") (pin "1") (pinfunction "1_1") (pintype "passive"))
      (node (ref "C17") (pin "2") (pinfunction "2_2") (pintype "passive"))
      (node (ref "C18") (pin "2") (pinfunction "2_2") (pintype "passive"))
      (node (ref "C19") (pin "2") (pinfunction "2_2") (pintype "passive"))
      (node (ref "C2") (pin "1") (pinfunction "1_1") (pintype "passive"))
      (node (ref "C20") (pin "1") (pinfunction "1_1") (pintype "passive"))
      (node (ref "C21") (pin "1") (pinfunction "1_1") (pintype "passive"))
      (node (ref "C22") (pin "1") (pinfunction "1_1") (pintype "passive"))
      (node (ref "C26") (pin "2") (pinfunction "2_2") (pintype "passive"))
      (node (ref "C27") (pin "2") (pinfunction "2_2") (pintype "passive"))
      (node (ref "C28") (pin "2") (pinfunction "2_2") (pintype "passive"))
      (node (ref "C29") (pin "2") (pinfunction "2_2") (pintype "passive"))
      (node (ref "C3") (pin "2") (pinfunction "2_2") (pintype "passive"))
      (node (ref "C30") (pin "2") (pinfunction "2_2") (pintype "passive"))
      (node (ref "C31") (pin "2") (pinfunction "2_2") (pintype "passive"))
      (node (ref "C32") (pin "2") (pinfunction "2_2") (pintype "passive"))
      (node (ref "C33") (pin "2") (pinfunction "2_2") (pintype "passive"))
      (node (ref "C5") (pin "2") (pinfunction "2_2") (pintype "passive"))
      (node (ref "C6") (pin "1") (pinfunction "1_1") (pintype "passive"))
      (node (ref "D5") (pin "2") (pinfunction "K_2") (pintype "passive"))
      (node (ref "D8") (pin "2") (pinfunction "K_2") (pintype "passive"))
      (node (ref "D9") (pin "2") (pinfunction "K_2") (pintype "passive"))
      (node (ref "DZ1") (pin "1") (pinfunction "A_1") (pintype "passive"))
      (node (ref "JP1") (pin "2") (pinfunction "2_2") (pintype "passive"))
      (node (ref "JP2") (pin "2") (pinfunction "2_2") (pintype "passive"))
      (node (ref "P4") (pin "5") (pinfunction "5_5") (pintype "passive"))
      (node (ref "Q1") (pin "1") (pinfunction "E_1") (pintype "passive"))
      (node (ref "R10") (pin "1") (pinfunction "1_1") (pintype "passive"))
      (node (ref "R11") (pin "2") (pinfunction "2_2") (pintype "passive"))
      (node (ref "R16") (pin "1") (pinfunction "1_1") (pintype "passive"))
      (node (ref "R20") (pin "1") (pinfunction "1_1") (pintype "passive"))
      (node (ref "R21") (pin "1") (pinfunction "1_1") (pintype "passive"))
      (node (ref "R27") (pin "1") (pinfunction "1_1") (pintype "passive"))
      (node (ref "R5") (pin "2") (pinfunction "2_2") (pintype "passive"))
      (node (ref "S1") (pin "5") (pinfunction "5_5") (pintype "passive"))
      (node (ref "S1") (pin "6") (pinfunction "6_6") (pintype "passive"))
      (node (ref "S1") (pin "7") (pinfunction "7_7") (pintype "passive"))
      (node (ref "S1") (pin "8") (pinfunction "8_8") (pintype "passive"))
      (node (ref "U1") (pin "16") (pinfunction "GND_16") (pintype "passive"))
      (node (ref "U2") (pin "3") (pinfunction "RSV2_3") (pintype "passive"))
      (node (ref "U2") (pin "33") (pinfunction "GNDD_33") (pintype "passive"))
      (node (ref "U2") (pin "8") (pinfunction "GNDD_8") (pintype "passive"))
      (node (ref "U4") (pin "2") (pinfunction "GND_2") (pintype "passive"))
      (node (ref "U5") (pin "23") (pinfunction "VSS_1_23") (pintype "power_in"))
      (node (ref "U5") (pin "35") (pinfunction "VSS_2_35") (pintype "power_in"))
      (node (ref "U5") (pin "47") (pinfunction "VSS_3_47") (pintype "power_in"))
      (node (ref "U5") (pin "8") (pinfunction "VSSA_8") (pintype "power_in"))
      (node (ref "U6") (pin "13") (pinfunction "GND_13") (pintype "passive"))
      (node (ref "U6") (pin "21") (pinfunction "GND_21") (pintype "passive"))
      (node (ref "U6") (pin "22") (pinfunction "GND_22") (pintype "passive"))
      (node (ref "U7") (pin "2") (pinfunction "GND_2") (pintype "passive"))
    )
    (net (code "76") (name "Net-(C7-Pad1)") (class "Default")
      (node (ref "C7") (pin "1") (pinfunction "1_1") (pintype "passive"))
      (node (ref "R8") (pin "2") (pinfunction "2_2") (pintype "passive"))
    )
    (net (code "77") (name "Net-(D1-A)") (class "Default")
      (node (ref "D1") (pin "1") (pinfunction "A_1") (pintype "passive"))
      (node (ref "R1") (pin "2") (pinfunction "2_2") (pintype "passive"))
    )
    (net (code "78") (name "Net-(D2-A)") (class "Default")
      (node (ref "D2") (pin "1") (pinfunction "A_1") (pintype "passive"))
      (node (ref "R2") (pin "1") (pinfunction "1_1") (pintype "passive"))
    )
    (net (code "79") (name "Net-(D2-K)") (class "Default")
      (node (ref "D2") (pin "2") (pinfunction "K_2") (pintype "passive"))
      (node (ref "U2") (pin "29") (pinfunction "RSV6_29") (pintype "passive"))
    )
    (net (code "80") (name "Net-(D3-A)") (class "Default")
      (node (ref "D3") (pin "1") (pinfunction "A_1") (pintype "passive"))
      (node (ref "R19") (pin "2") (pinfunction "2_2") (pintype "passive"))
    )
    (net (code "81") (name "Net-(D4-A)") (class "Default")
      (node (ref "D4") (pin "1") (pinfunction "A_1") (pintype "passive"))
      (node (ref "R13") (pin "2") (pinfunction "2_2") (pintype "passive"))
    )
    (net (code "82") (name "Net-(D5-A)") (class "Default")
      (node (ref "D5") (pin "1") (pinfunction "A_1") (pintype "passive"))
      (node (ref "R17") (pin "2") (pinfunction "2_2") (pintype "passive"))
    )
    (net (code "83") (name "Net-(D8-A)") (class "Default")
      (node (ref "D8") (pin "1") (pinfunction "A_1") (pintype "passive"))
      (node (ref "R29") (pin "1") (pinfunction "1_1") (pintype "passive"))
    )
    (net (code "84") (name "Net-(D9-A)") (class "Default")
      (node (ref "D9") (pin "1") (pinfunction "A_1") (pintype "passive"))
      (node (ref "R23") (pin "2") (pinfunction "2_2") (pintype "passive"))
    )
    (net (code "85") (name "Net-(LS1-A)") (class "Default")
      (node (ref "LS1") (pin "1") (pinfunction "A_1") (pintype "passive"))
      (node (ref "Q1") (pin "3") (pinfunction "C_3") (pintype "passive"))
    )
    (net (code "86") (name "Net-(P4-Pad3)") (class "Default")
      (node (ref "P4") (pin "3") (pinfunction "3_3") (pintype "passive"))
      (node (ref "R13") (pin "1") (pinfunction "1_1") (pintype "passive"))
      (node (ref "R14") (pin "1") (pinfunction "1_1") (pintype "passive"))
    )
    (net (code "87") (name "Net-(P4-Pad4)") (class "Default")
      (node (ref "P4") (pin "4") (pinfunction "4_4") (pintype "passive"))
      (node (ref "R12") (pin "1") (pinfunction "1_1") (pintype "passive"))
    )
    (net (code "88") (name "Net-(Q1-B)") (class "Default")
      (node (ref "Q1") (pin "2") (pinfunction "B_2") (pintype "passive"))
      (node (ref "R15") (pin "2") (pinfunction "2_2") (pintype "passive"))
    )
    (net (code "89") (name "Net-(U2-EQ1)") (class "Default")
      (node (ref "C7") (pin "2") (pinfunction "2_2") (pintype "passive"))
      (node (ref "U2") (pin "20") (pinfunction "EQ1_20") (pintype "passive"))
    )
    (net (code "90") (name "Net-(U2-EQ2)") (class "Default")
      (node (ref "C9") (pin "2") (pinfunction "2_2") (pintype "passive"))
      (node (ref "R8") (pin "1") (pinfunction "1_1") (pintype "passive"))
      (node (ref "R9") (pin "2") (pinfunction "2_2") (pintype "passive"))
      (node (ref "U2") (pin "21") (pinfunction "EQ2_21") (pintype "passive"))
    )
    (net (code "91") (name "Net-(U2-EQ3)") (class "Default")
      (node (ref "C9") (pin "1") (pinfunction "1_1") (pintype "passive"))
      (node (ref "R9") (pin "1") (pinfunction "1_1") (pintype "passive"))
      (node (ref "U2") (pin "22") (pinfunction "EQ3_22") (pintype "passive"))
    )
    (net (code "92") (name "Net-(U5A-BOOT0)") (class "Default")
      (node (ref "R21") (pin "2") (pinfunction "2_2") (pintype "passive"))
      (node (ref "U5") (pin "44") (pinfunction "BOOT0_44") (pintype "input"))
    )
    (net (code "93") (name "Net-(U5A-PB2)") (class "Default")
      (node (ref "R20") (pin "2") (pinfunction "2_2") (pintype "passive"))
      (node (ref "U5") (pin "20") (pinfunction "PB2_20") (pintype "bidirectional"))
    )
    (net (code "94") (name "Net-(U6-PIO8)") (class "Default")
      (node (ref "R29") (pin "2") (pinfunction "2_2") (pintype "passive"))
      (node (ref "U6") (pin "31") (pinfunction "PIO8_31") (pintype "passive"))
    )
    (net (code "95") (name "Net-(U6-PIO9)") (class "Default")
      (node (ref "R28") (pin "2") (pinfunction "2_2") (pintype "passive"))
      (node (ref "U6") (pin "32") (pinfunction "PIO9_32") (pintype "passive"))
    )
    (net (code "96") (name "Net-(U6-PIO11)") (class "Default")
      (node (ref "R26") (pin "2") (pinfunction "2_2") (pintype "passive"))
      (node (ref "R27") (pin "2") (pinfunction "2_2") (pintype "passive"))
      (node (ref "U6") (pin "34") (pinfunction "PIO11_34") (pintype "passive"))
    )
    (net (code "97") (name "Net-(U6-UART_RXD)") (class "Default")
      (node (ref "D7") (pin "2") (pintype "passive"))
      (node (ref "R25") (pin "2") (pinfunction "2_2") (pintype "passive"))
      (node (ref "U6") (pin "2") (pinfunction "UART_RXD_2") (pintype "passive"))
    )
    (net (code "98") (name "Net-(U6-UART_TXD)") (class "Default")
      (node (ref "D6") (pin "1") (pintype "passive"))
      (node (ref "U6") (pin "1") (pinfunction "UART_TXD_1") (pintype "passive"))
    )
    (net (code "99") (name "Net-(U7-BP)") (class "Default")
      (node (ref "C33") (pin "1") (pinfunction "1_1") (pintype "passive"))
      (node (ref "U7") (pin "4") (pinfunction "BP_4") (pintype "passive"))
    )
    (net (code "100") (name "PWR_3V3") (class "Default")
      (node (ref "C16") (pin "2") (pinfunction "2_2") (pintype "passive"))
      (node (ref "C17") (pin "1") (pinfunction "1_1") (pintype "passive"))
      (node (ref "C19") (pin "1") (pinfunction "1_1") (pintype "passive"))
      (node (ref "C2") (pin "2") (pinfunction "2_2") (pintype "passive"))
      (node (ref "C23") (pin "2") (pinfunction "2_2") (pintype "passive"))
      (node (ref "C26") (pin "1") (pinfunction "1_1") (pintype "passive"))
      (node (ref "C27") (pin "1") (pinfunction "1_1") (pintype "passive"))
      (node (ref "C28") (pin "1") (pinfunction "1_1") (pintype "passive"))
      (node (ref "C29") (pin "1") (pinfunction "1_1") (pintype "passive"))
      (node (ref "C3") (pin "1") (pinfunction "1_1") (pintype "passive"))
      (node (ref "C32") (pin "1") (pinfunction "1_1") (pintype "passive"))
      (node (ref "L1") (pin "2") (pinfunction "2_2") (pintype "passive"))
      (node (ref "P4") (pin "1") (pinfunction "1_1") (pintype "passive"))
      (node (ref "R1") (pin "1") (pinfunction "1_1") (pintype "passive"))
      (node (ref "R14") (pin "2") (pinfunction "2_2") (pintype "passive"))
      (node (ref "R19") (pin "1") (pinfunction "1_1") (pintype "passive"))
      (node (ref "R2") (pin "2") (pinfunction "2_2") (pintype "passive"))
      (node (ref "R22") (pin "1") (pinfunction "1_1") (pintype "passive"))
      (node (ref "R23") (pin "1") (pinfunction "1_1") (pintype "passive"))
      (node (ref "R24") (pin "1") (pinfunction "1_1") (pintype "passive"))
      (node (ref "R6") (pin "1") (pinfunction "1_1") (pintype "passive"))
      (node (ref "R7") (pin "1") (pinfunction "1_1") (pintype "passive"))
      (node (ref "S2") (pin "1") (pinfunction "1_1") (pintype "passive"))
      (node (ref "U1") (pin "38") (pinfunction "VCC_38") (pintype "passive"))
      (node (ref "U2") (pin "1") (pinfunction "VCC_1") (pintype "passive"))
      (node (ref "U2") (pin "32") (pinfunction "VCC_32") (pintype "passive"))
      (node (ref "U2") (pin "7") (pinfunction "VCC_7") (pintype "passive"))
      (node (ref "U4") (pin "3") (pinfunction "Vout_3") (pintype "passive"))
      (node (ref "U5") (pin "1") (pinfunction "VBAT_1") (pintype "power_in"))
      (node (ref "U5") (pin "24") (pinfunction "VDD_1_24") (pintype "power_in"))
      (node (ref "U5") (pin "36") (pinfunction "VDD_2_36") (pintype "power_in"))
      (node (ref "U5") (pin "48") (pinfunction "VDD_3_48") (pintype "power_in"))
      (node (ref "U5") (pin "9") (pinfunction "VDDA_9") (pintype "power_in"))
      (node (ref "U7") (pin "1") (pinfunction "VIN_1") (pintype "passive"))
      (node (ref "U7") (pin "3") (pinfunction "EN_3") (pintype "passive"))
    )
    (net (code "101") (name "VBAT_6V") (class "Default")
      (node (ref "JP1") (pin "1") (pinfunction "1_1") (pintype "passive"))
      (node (ref "R18") (pin "2") (pinfunction "2_2") (pintype "passive"))
    )
    (net (code "102") (name "VDDA") (class "Default")
      (node (ref "C11") (pin "1") (pinfunction "1_1") (pintype "passive"))
      (node (ref "C12") (pin "2") (pinfunction "2_2") (pintype "passive"))
      (node (ref "C14") (pin "2") (pinfunction "2_2") (pintype "passive"))
      (node (ref "C15") (pin "2") (pinfunction "2_2") (pintype "passive"))
      (node (ref "L1") (pin "1") (pinfunction "1_1") (pintype "passive"))
      (node (ref "U2") (pin "18") (pinfunction "VREF_18") (pintype "passive"))
      (node (ref "U2") (pin "19") (pinfunction "VDDA_19") (pintype "passive"))
      (node (ref "U2") (pin "23") (pinfunction "VDDA_23") (pintype "passive"))
    )
    (net (code "103") (name "VIN_5V") (class "Default")
      (node (ref "C18") (pin "1") (pinfunction "1_1") (pintype "passive"))
      (node (ref "C20") (pin "2") (pinfunction "2_2") (pintype "passive"))
      (node (ref "DZ1") (pin "2") (pinfunction "K_2") (pintype "passive"))
      (node (ref "JP2") (pin "1") (pinfunction "1_1") (pintype "passive"))
      (node (ref "LS1") (pin "2") (pinfunction "B_2") (pintype "passive"))
      (node (ref "P4") (pin "2") (pinfunction "2_2") (pintype "passive"))
      (node (ref "R18") (pin "1") (pinfunction "1_1") (pintype "passive"))
      (node (ref "U4") (pin "1") (pinfunction "Vin_1") (pintype "passive"))
    )
    (net (code "104") (name "unconnected-(U1-ALE-Pad27)") (class "Default")
      (node (ref "U1") (pin "27") (pinfunction "ALE_27") (pintype "passive+no_connect"))
    )
    (net (code "105") (name "unconnected-(U1-NA-Pad29)") (class "Default")
      (node (ref "U1") (pin "29") (pinfunction "NA_29") (pintype "passive+no_connect"))
    )
    (net (code "106") (name "unconnected-(U1-P2.2-Pad20)") (class "Default")
      (node (ref "U1") (pin "20") (pinfunction "P2.2_20") (pintype "passive+no_connect"))
    )
    (net (code "107") (name "unconnected-(U1-P4.0-Pad17)") (class "Default")
      (node (ref "U1") (pin "17") (pinfunction "P4.0_17") (pintype "passive+no_connect"))
    )
    (net (code "108") (name "unconnected-(U1-PESN-Pad26)") (class "Default")
      (node (ref "U1") (pin "26") (pinfunction "PESN_26") (pintype "passive+no_connect"))
    )
    (net (code "109") (name "unconnected-(U2-HPOL-Pad15)") (class "Default")
      (node (ref "U2") (pin "15") (pinfunction "HPOL_15") (pintype "passive+no_connect"))
    )
    (net (code "110") (name "unconnected-(U2-HPOR-Pad16)") (class "Default")
      (node (ref "U2") (pin "16") (pinfunction "HPOR_16") (pintype "passive+no_connect"))
    )
    (net (code "111") (name "unconnected-(U2-LOUTL-Pad27)") (class "Default")
      (node (ref "U2") (pin "27") (pinfunction "LOUTL_27") (pintype "passive+no_connect"))
    )
    (net (code "112") (name "unconnected-(U2-LOUTR-Pad28)") (class "Default")
      (node (ref "U2") (pin "28") (pinfunction "LOUTR_28") (pintype "passive+no_connect"))
    )
    (net (code "113") (name "unconnected-(U2-RSV1-Pad2)") (class "Default")
      (node (ref "U2") (pin "2") (pinfunction "RSV1_2") (pintype "passive+no_connect"))
    )
    (net (code "114") (name "unconnected-(U2-RSV3-Pad4)") (class "Default")
      (node (ref "U2") (pin "4") (pinfunction "RSV3_4") (pintype "passive+no_connect"))
    )
    (net (code "115") (name "unconnected-(U2-RSV4-Pad5)") (class "Default")
      (node (ref "U2") (pin "5") (pinfunction "RSV4_5") (pintype "passive+no_connect"))
    )
    (net (code "116") (name "unconnected-(U2-RSV5=NC-Pad6)") (class "Default")
      (node (ref "U2") (pin "6") (pinfunction "RSV5=NC_6") (pintype "passive+no_connect"))
    )
    (net (code "117") (name "unconnected-(U2-RSV7-Pad30)") (class "Default")
      (node (ref "U2") (pin "30") (pinfunction "RSV7_30") (pintype "passive+no_connect"))
    )
    (net (code "118") (name "unconnected-(U5A-PA12-Pad33)") (class "Default")
      (node (ref "U5") (pin "33") (pinfunction "PA12_33") (pintype "bidirectional+no_connect"))
    )
    (net (code "119") (name "unconnected-(U5A-PA15-Pad38)") (class "Default")
      (node (ref "U5") (pin "38") (pinfunction "PA15_38") (pintype "bidirectional+no_connect"))
    )
    (net (code "120") (name "unconnected-(U5A-PB8-Pad45)") (class "Default")
      (node (ref "U5") (pin "45") (pinfunction "PB8_45") (pintype "bidirectional+no_connect"))
    )
    (net (code "121") (name "unconnected-(U5A-PB9-Pad46)") (class "Default")
      (node (ref "U5") (pin "46") (pinfunction "PB9_46") (pintype "bidirectional+no_connect"))
    )
    (net (code "122") (name "unconnected-(U5A-PB14-Pad27)") (class "Default")
      (node (ref "U5") (pin "27") (pinfunction "PB14_27") (pintype "bidirectional+no_connect"))
    )
    (net (code "123") (name "unconnected-(U5A-PB15-Pad28)") (class "Default")
      (node (ref "U5") (pin "28") (pinfunction "PB15_28") (pintype "bidirectional+no_connect"))
    )
    (net (code "124") (name "unconnected-(U5A-PC13-TAMPER-RTC-Pad2)") (class "Default")
      (node (ref "U5") (pin "2") (pinfunction "PC13-TAMPER-RTC_2") (pintype "bidirectional+no_connect"))
    )
    (net (code "125") (name "unconnected-(U5A-PC14-OSC32_IN-Pad3)") (class "Default")
      (node (ref "U5") (pin "3") (pinfunction "PC14-OSC32_IN_3") (pintype "bidirectional+no_connect"))
    )
    (net (code "126") (name "unconnected-(U5A-PC15-OSC32_OUT-Pad4)") (class "Default")
      (node (ref "U5") (pin "4") (pinfunction "PC15-OSC32_OUT_4") (pintype "bidirectional+no_connect"))
    )
    (net (code "127") (name "unconnected-(U6-AIO0-Pad9)") (class "Default")
      (node (ref "U6") (pin "9") (pinfunction "AIO0_9") (pintype "passive+no_connect"))
    )
    (net (code "128") (name "unconnected-(U6-AIO1-Pad10)") (class "Default")
      (node (ref "U6") (pin "10") (pinfunction "AIO1_10") (pintype "passive+no_connect"))
    )
    (net (code "129") (name "unconnected-(U6-CLK-Pad19)") (class "Default")
      (node (ref "U6") (pin "19") (pinfunction "CLK_19") (pintype "passive+no_connect"))
    )
    (net (code "130") (name "unconnected-(U6-CSB-Pad16)") (class "Default")
      (node (ref "U6") (pin "16") (pinfunction "CSB_16") (pintype "passive+no_connect"))
    )
    (net (code "131") (name "unconnected-(U6-D+-Pad20)") (class "Default")
      (node (ref "U6") (pin "20") (pinfunction "D+_20") (pintype "passive+no_connect"))
    )
    (net (code "132") (name "unconnected-(U6-D--Pad15)") (class "Default")
      (node (ref "U6") (pin "15") (pinfunction "D-_15") (pintype "passive+no_connect"))
    )
    (net (code "133") (name "unconnected-(U6-MISO-Pad18)") (class "Default")
      (node (ref "U6") (pin "18") (pinfunction "MISO_18") (pintype "passive+no_connect"))
    )
    (net (code "134") (name "unconnected-(U6-MOSI-Pad17)") (class "Default")
      (node (ref "U6") (pin "17") (pinfunction "MOSI_17") (pintype "passive+no_connect"))
    )
    (net (code "135") (name "unconnected-(U6-NC-Pad14)") (class "Default")
      (node (ref "U6") (pin "14") (pinfunction "NC_14") (pintype "passive+no_connect"))
    )
    (net (code "136") (name "unconnected-(U6-PCM_CLK-Pad5)") (class "Default")
      (node (ref "U6") (pin "5") (pinfunction "PCM_CLK_5") (pintype "passive+no_connect"))
    )
    (net (code "137") (name "unconnected-(U6-PCM_IN-Pad7)") (class "Default")
      (node (ref "U6") (pin "7") (pinfunction "PCM_IN_7") (pintype "passive+no_connect"))
    )
    (net (code "138") (name "unconnected-(U6-PCM_OUT-Pad6)") (class "Default")
      (node (ref "U6") (pin "6") (pinfunction "PCM_OUT_6") (pintype "passive+no_connect"))
    )
    (net (code "139") (name "unconnected-(U6-PCM_SYNC-Pad8)") (class "Default")
      (node (ref "U6") (pin "8") (pinfunction "PCM_SYNC_8") (pintype "passive+no_connect"))
    )
    (net (code "140") (name "unconnected-(U6-PIO0-Pad23)") (class "Default")
      (node (ref "U6") (pin "23") (pinfunction "PIO0_23") (pintype "passive+no_connect"))
    )
    (net (code "141") (name "unconnected-(U6-PIO1-Pad24)") (class "Default")
      (node (ref "U6") (pin "24") (pinfunction "PIO1_24") (pintype "passive+no_connect"))
    )
    (net (code "142") (name "unconnected-(U6-PIO2-Pad25)") (class "Default")
      (node (ref "U6") (pin "25") (pinfunction "PIO2_25") (pintype "passive+no_connect"))
    )
    (net (code "143") (name "unconnected-(U6-PIO3-Pad26)") (class "Default")
      (node (ref "U6") (pin "26") (pinfunction "PIO3_26") (pintype "passive+no_connect"))
    )
    (net (code "144") (name "unconnected-(U6-PIO4-Pad27)") (class "Default")
      (node (ref "U6") (pin "27") (pinfunction "PIO4_27") (pintype "passive+no_connect"))
    )
    (net (code "145") (name "unconnected-(U6-PIO5-Pad28)") (class "Default")
      (node (ref "U6") (pin "28") (pinfunction "PIO5_28") (pintype "passive+no_connect"))
    )
    (net (code "146") (name "unconnected-(U6-PIO6-Pad29)") (class "Default")
      (node (ref "U6") (pin "29") (pinfunction "PIO6_29") (pintype "passive+no_connect"))
    )
    (net (code "147") (name "unconnected-(U6-PIO7-Pad30)") (class "Default")
      (node (ref "U6") (pin "30") (pinfunction "PIO7_30") (pintype "passive+no_connect"))
    )
    (net (code "148") (name "unconnected-(U6-PIO10-Pad33)") (class "Default")
      (node (ref "U6") (pin "33") (pinfunction "PIO10_33") (pintype "passive+no_connect"))
    )
    (net (code "149") (name "unconnected-(U6-RESET-Pad11)") (class "Default")
      (node (ref "U6") (pin "11") (pinfunction "RESET_11") (pintype "passive+no_connect"))
    )
    (net (code "150") (name "unconnected-(U6-UART_CTS-Pad3)") (class "Default")
      (node (ref "U6") (pin "3") (pinfunction "UART_CTS_3") (pintype "passive+no_connect"))
    )
    (net (code "151") (name "unconnected-(U6-UART_RTS-Pad4)") (class "Default")
      (node (ref "U6") (pin "4") (pinfunction "UART_RTS_4") (pintype "passive+no_connect"))
    )
  )
)
